# ProPrj_TPS53318-__2025-09-09_17-23-30_20.net
KiCad netlist of a schematic drawn in EasyEDA Pro
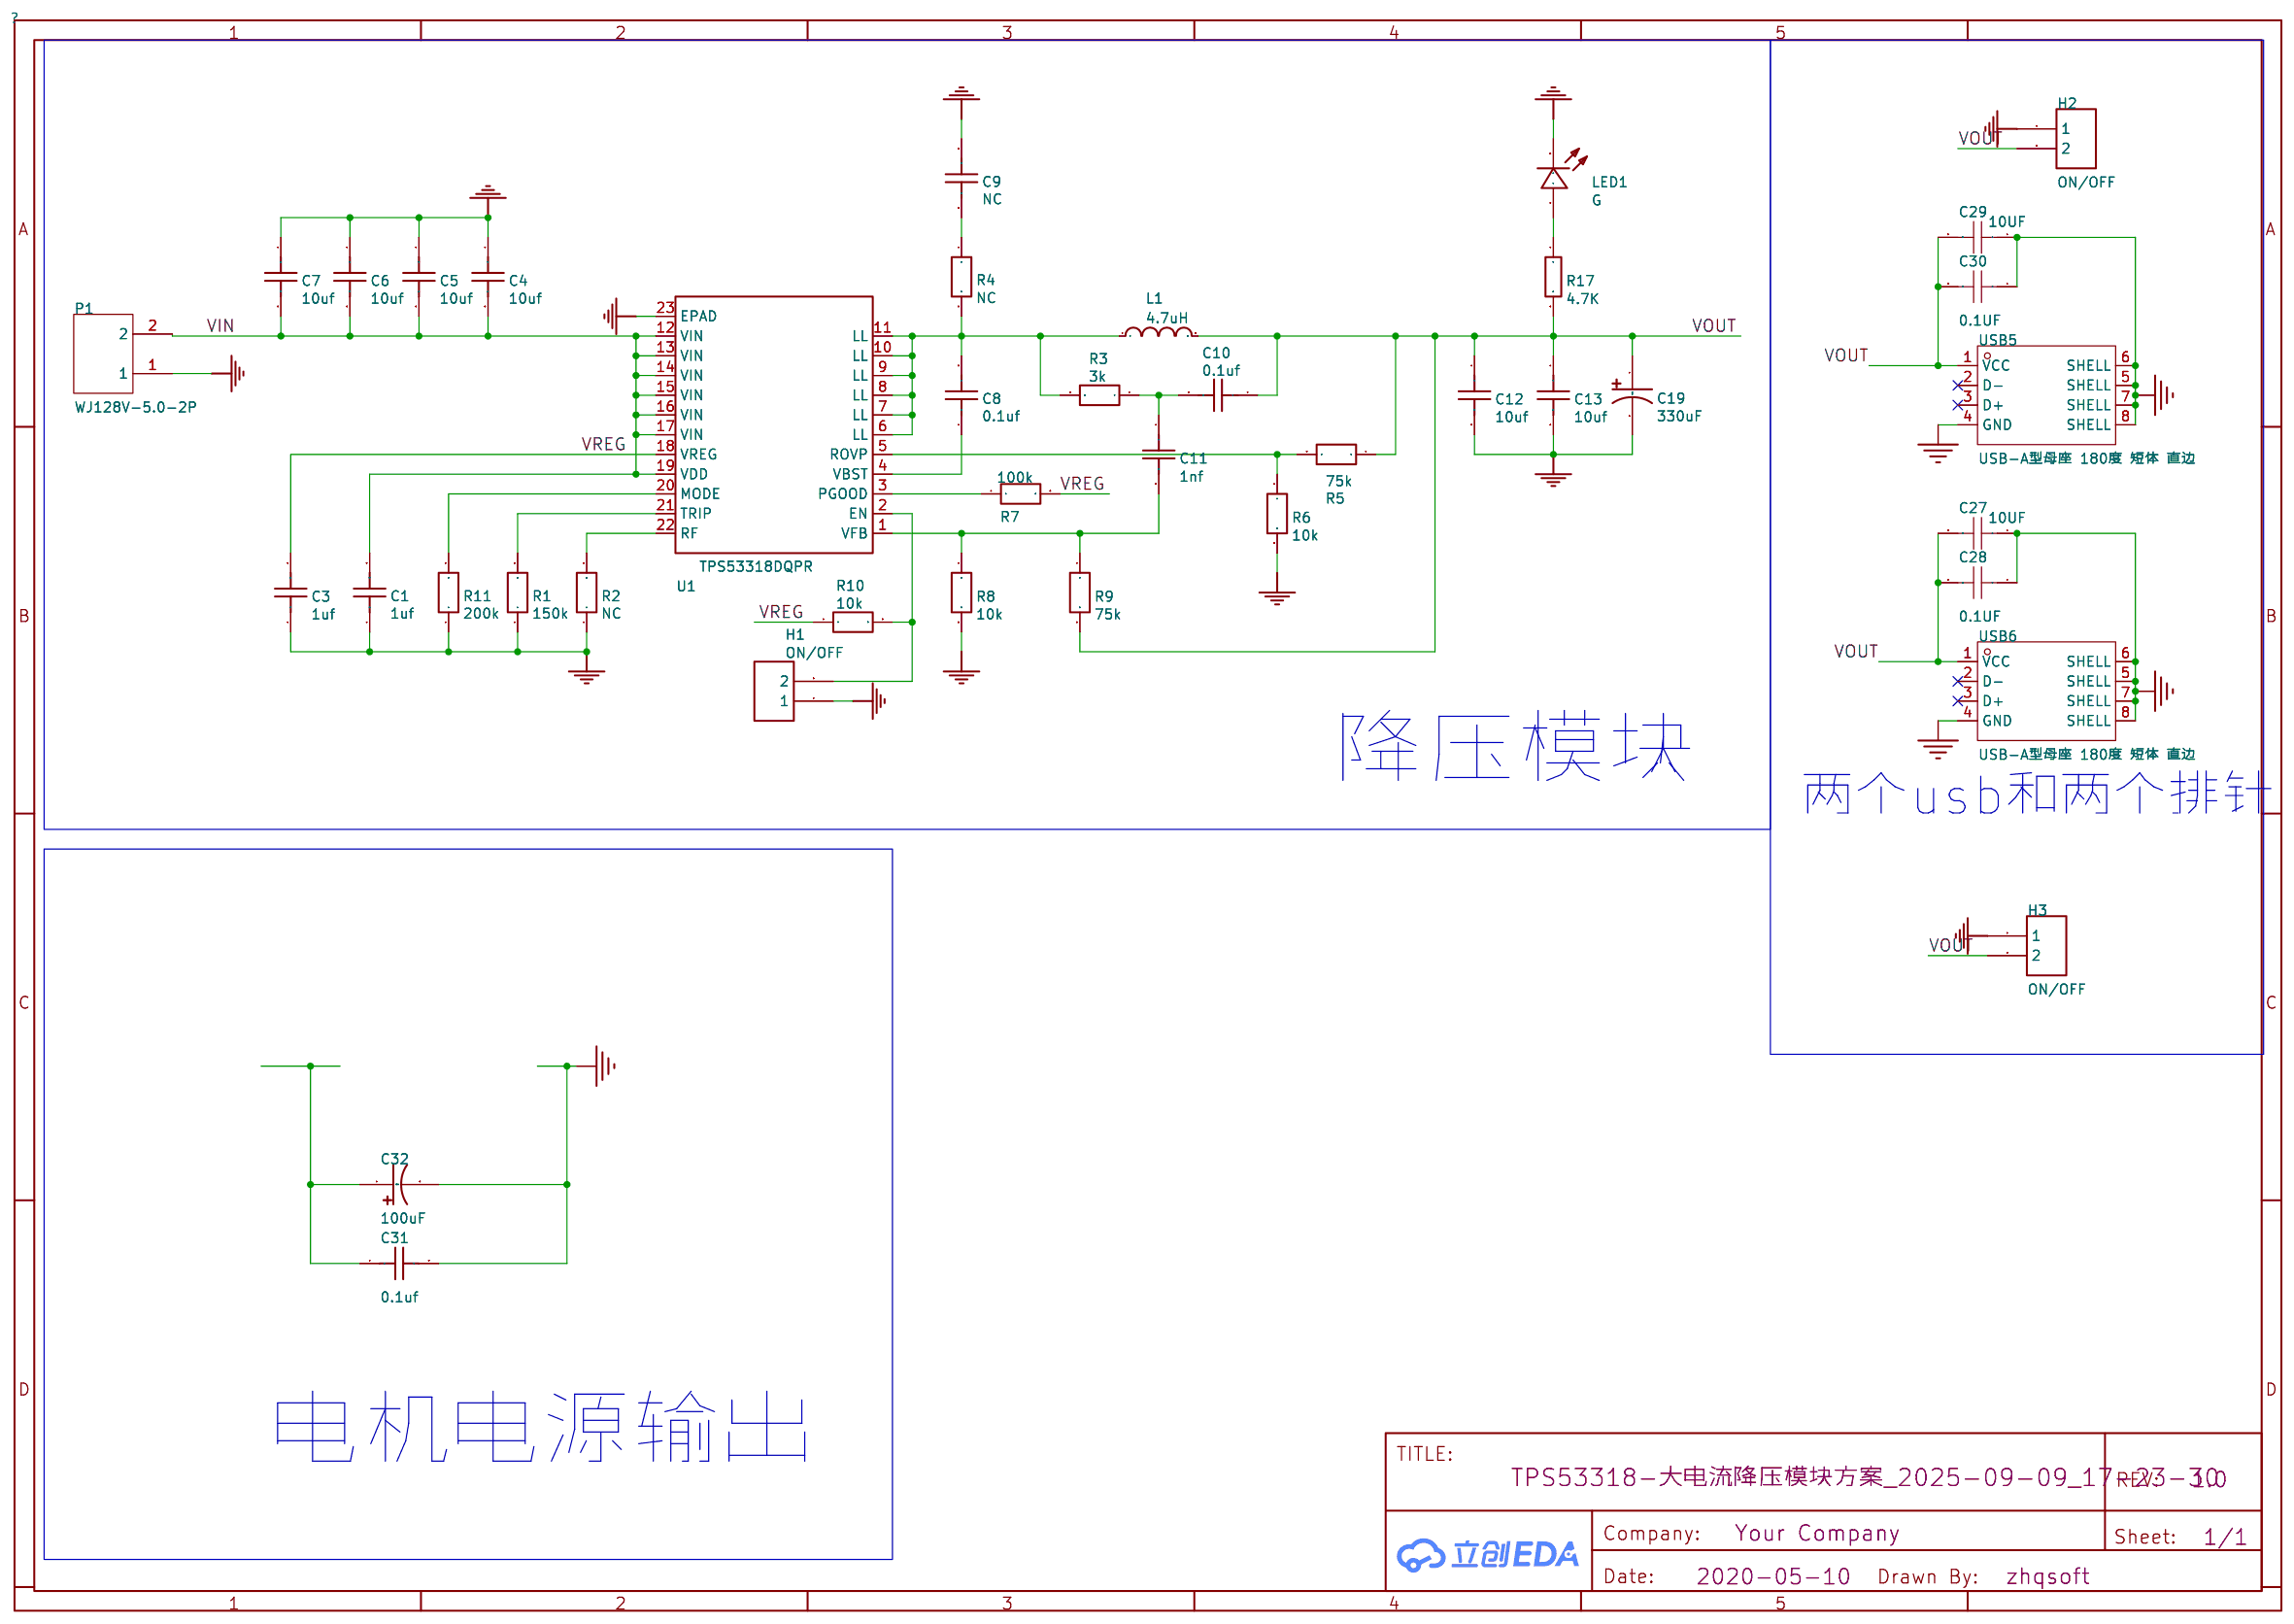
[diagram p0: schematic sheet]

(export (version "E")
  (design (tool "Eeschema 10.0.6"))
  (components
    (comp (ref "C1")
      (value "1uf")
      (fields (field (name "Contributor") "LCEDA_Lib"))
      (libsource (lib "easyedapro") (part "1uf"))
    )
    (comp (ref "C3")
      (value "1uf")
      (fields (field (name "Contributor") "LCEDA_Lib"))
      (libsource (lib "easyedapro") (part "1uf"))
    )
    (comp (ref "C4")
      (value "10uf")
      (fields (field (name "Contributor") "LCEDA_Lib"))
      (libsource (lib "easyedapro") (part "10uf"))
    )
    (comp (ref "C5")
      (value "10uf")
      (fields (field (name "Contributor") "LCEDA_Lib"))
      (libsource (lib "easyedapro") (part "10uf"))
    )
    (comp (ref "C6")
      (value "10uf")
      (fields (field (name "Contributor") "LCEDA_Lib"))
      (libsource (lib "easyedapro") (part "10uf"))
    )
    (comp (ref "C7")
      (value "10uf")
      (fields (field (name "Contributor") "LCEDA_Lib"))
      (libsource (lib "easyedapro") (part "10uf"))
    )
    (comp (ref "C8")
      (value "0.1uf")
      (fields (field (name "Contributor") "LCEDA_Lib"))
      (libsource (lib "easyedapro") (part "0.1uf"))
    )
    (comp (ref "C9")
      (value "NC")
      (fields (field (name "Contributor") "LCEDA_Lib"))
      (libsource (lib "") (part "NC_1"))
    )
    (comp (ref "C10")
      (value "0.1uf")
      (fields (field (name "Contributor") "LCEDA_Lib"))
      (libsource (lib "easyedapro") (part "0.1uf"))
    )
    (comp (ref "C11")
      (value "1nf")
      (fields (field (name "Contributor") "LCEDA_Lib"))
      (libsource (lib "easyedapro") (part "1nf"))
    )
    (comp (ref "C12")
      (value "10uf")
      (fields (field (name "Contributor") "LCEDA_Lib"))
      (libsource (lib "easyedapro") (part "10uf"))
    )
    (comp (ref "C13")
      (value "10uf")
      (fields (field (name "Contributor") "LCEDA_Lib"))
      (libsource (lib "easyedapro") (part "10uf"))
    )
    (comp (ref "C19")
      (value "330uF")
      (fields
        (field (name "Manufacturer Part") "OVZ331M0JTR-0606")
        (field (name "Manufacturer") "LELON")
        (field (name "Contributor") "LCSC")
      )
      (libsource (lib "easyedapro") (part "330uF"))
    )
    (comp (ref "C27")
      (value "10UF")
      (footprint "easyedapro:C0805")
      (libsource (lib "easyedapro") (part "CapAcitance"))
    )
    (comp (ref "C28")
      (value "0.1UF")
      (footprint "easyedapro:C0805")
      (libsource (lib "easyedapro") (part "CapAcitance"))
    )
    (comp (ref "C29")
      (value "10UF")
      (footprint "easyedapro:C0805")
      (libsource (lib "easyedapro") (part "CapAcitance"))
    )
    (comp (ref "C30")
      (value "0.1UF")
      (footprint "easyedapro:C0805")
      (libsource (lib "easyedapro") (part "CapAcitance"))
    )
    (comp (ref "C31")
      (value "0.1uf")
      (fields (field (name "Contributor") "LCEDA_Lib"))
      (libsource (lib "easyedapro") (part "10uf"))
    )
    (comp (ref "C32")
      (value "100uF")
      (fields
        (field (name "Manufacturer Part") "OVZ331M0JTR-0606")
        (field (name "Manufacturer") "LELON")
        (field (name "Contributor") "LCSC")
      )
      (libsource (lib "easyedapro") (part "330uF"))
    )
    (comp (ref "H1")
      (value "ON/OFF")
      (fields (field (name "Manufacturer Part") "3-644456-2") (field (name "Manufacturer") "TE Connectivity"))
      (libsource (lib "easyedapro") (part "ON/OFF"))
    )
    (comp (ref "H2")
      (value "ON/OFF")
      (fields (field (name "Manufacturer Part") "3-644456-2") (field (name "Manufacturer") "TE Connectivity"))
      (libsource (lib "easyedapro") (part "ON/OFF"))
    )
    (comp (ref "H3")
      (value "ON/OFF")
      (fields (field (name "Manufacturer Part") "3-644456-2") (field (name "Manufacturer") "TE Connectivity"))
      (libsource (lib "easyedapro") (part "ON/OFF"))
    )
    (comp (ref "L1")
      (value "4.7uH")
      (fields (field (name "Manufacturer Part") "SMMS1040-4R7M") (field (name "Manufacturer") "SXN"))
      (libsource (lib "easyedapro") (part "4.7uH"))
    )
    (comp (ref "LED1")
      (value "G")
      (fields
        (field (name "Manufacturer Part") "ORH-G36G")
        (field (name "Manufacturer") "Orient")
        (field (name "Contributor") "LCSC")
      )
      (libsource (lib "easyedapro") (part "G"))
    )
    (comp (ref "P1")
      (value "WJ128V-5.0-2P")
      (footprint "easyedapro:CONN-TH_2P-P5.00_WJ128V-5.0-2P")
      (fields (field (name "Manufacturer") "KANGNEX(康奈克斯电气)"))
      (libsource (lib "easyedapro") (part "WJ128V-5.0-2P"))
    )
    (comp (ref "R1")
      (value "150k")
      (fields (field (name "Contributor") "LCEDA_Lib"))
      (libsource (lib "easyedapro") (part "150k"))
    )
    (comp (ref "R2")
      (value "NC")
      (fields (field (name "Contributor") "LCEDA_Lib"))
      (libsource (lib "") (part "NC_2"))
    )
    (comp (ref "R3")
      (value "3k")
      (fields (field (name "Contributor") "LCEDA_Lib"))
      (libsource (lib "easyedapro") (part "3k"))
    )
    (comp (ref "R4")
      (value "NC")
      (fields (field (name "Contributor") "LCEDA_Lib"))
      (libsource (lib "easyedapro") (part "NC"))
    )
    (comp (ref "R5")
      (value "75k")
      (fields (field (name "Contributor") "LCEDA_Lib"))
      (libsource (lib "") (part "75k_1"))
    )
    (comp (ref "R6")
      (value "10k")
      (fields (field (name "Contributor") "LCEDA_Lib"))
      (libsource (lib "easyedapro") (part "10k"))
    )
    (comp (ref "R7")
      (value "100k")
      (fields (field (name "Contributor") "LCEDA_Lib"))
      (libsource (lib "easyedapro") (part "100k"))
    )
    (comp (ref "R8")
      (value "10k")
      (fields (field (name "Contributor") "LCEDA_Lib"))
      (libsource (lib "easyedapro") (part "10k"))
    )
    (comp (ref "R9")
      (value "75k")
      (fields (field (name "Contributor") "LCEDA_Lib"))
      (libsource (lib "easyedapro") (part "75k"))
    )
    (comp (ref "R10")
      (value "10k")
      (fields (field (name "Contributor") "LCEDA_Lib"))
      (libsource (lib "") (part "10k_1"))
    )
    (comp (ref "R11")
      (value "200k")
      (fields (field (name "Contributor") "LCEDA_Lib"))
      (libsource (lib "easyedapro") (part "200k"))
    )
    (comp (ref "R17")
      (value "4.7K")
      (fields
        (field (name "Manufacturer Part") "WR04X4701FTL")
        (field (name "Manufacturer") "WALSIN")
        (field (name "Contributor") "LCSC")
      )
      (libsource (lib "easyedapro") (part "4.7K"))
    )
    (comp (ref "U1")
      (value "TPS53318DQPR")
      (fields (field (name "Manufacturer") "Texas Instruments") (field (name "Contributor") "LCSC"))
      (libsource (lib "easyedapro") (part "TPS53318DQPR"))
    )
    (comp (ref "USB5")
      (value "USB-A型母座 180度 短体 直边")
      (footprint "easyedapro:USB-A-SMD_WT_C9900004571")
      (libsource (lib "easyedapro") (part "USB-A型母座 180度 短体 直边"))
    )
    (comp (ref "USB6")
      (value "USB-A型母座 180度 短体 直边")
      (footprint "easyedapro:USB-A-SMD_WT_C9900004571")
      (libsource (lib "easyedapro") (part "USB-A型母座 180度 短体 直边"))
    )
  )
  (nets
    (net (code "1") (name "/VIN") (class "Default")
      (node (ref "C1") (pin "2") (pinfunction "2_2") (pintype "unspecified"))
      (node (ref "C4") (pin "2") (pinfunction "2_2") (pintype "unspecified"))
      (node (ref "C5") (pin "2") (pinfunction "2_2") (pintype "unspecified"))
      (node (ref "C6") (pin "2") (pinfunction "2_2") (pintype "unspecified"))
      (node (ref "C7") (pin "2") (pinfunction "2_2") (pintype "unspecified"))
      (node (ref "P1") (pin "2") (pinfunction "2_2") (pintype "unspecified"))
      (node (ref "U1") (pin "12") (pinfunction "VIN_12") (pintype "unspecified"))
      (node (ref "U1") (pin "13") (pinfunction "VIN_13") (pintype "unspecified"))
      (node (ref "U1") (pin "14") (pinfunction "VIN_14") (pintype "unspecified"))
      (node (ref "U1") (pin "15") (pinfunction "VIN_15") (pintype "unspecified"))
      (node (ref "U1") (pin "16") (pinfunction "VIN_16") (pintype "unspecified"))
      (node (ref "U1") (pin "17") (pinfunction "VIN_17") (pintype "unspecified"))
      (node (ref "U1") (pin "19") (pinfunction "VDD_19") (pintype "unspecified"))
    )
    (net (code "2") (name "/VOUT") (class "Default")
      (node (ref "C10") (pin "1") (pinfunction "1_1") (pintype "unspecified"))
      (node (ref "C12") (pin "1") (pinfunction "1_1") (pintype "unspecified"))
      (node (ref "C13") (pin "1") (pinfunction "1_1") (pintype "unspecified"))
      (node (ref "C19") (pin "1") (pinfunction "1_1") (pintype "unspecified"))
      (node (ref "C27") (pin "2") (pinfunction "2_2") (pintype "input"))
      (node (ref "C28") (pin "2") (pinfunction "2_2") (pintype "input"))
      (node (ref "C29") (pin "2") (pinfunction "2_2") (pintype "input"))
      (node (ref "C30") (pin "2") (pinfunction "2_2") (pintype "input"))
      (node (ref "H2") (pin "2") (pinfunction "2_2") (pintype "input"))
      (node (ref "H3") (pin "2") (pinfunction "2_2") (pintype "input"))
      (node (ref "L1") (pin "2") (pinfunction "2_2") (pintype "unspecified"))
      (node (ref "R17") (pin "2") (pinfunction "2_2") (pintype "unspecified"))
      (node (ref "R5") (pin "1") (pinfunction "1_1") (pintype "unspecified"))
      (node (ref "R9") (pin "2") (pinfunction "2_2") (pintype "unspecified"))
      (node (ref "USB5") (pin "1") (pinfunction "VCC_1") (pintype "unspecified"))
      (node (ref "USB6") (pin "1") (pinfunction "VCC_1") (pintype "unspecified"))
    )
    (net (code "3") (name "/VREG") (class "Default")
      (node (ref "C3") (pin "2") (pinfunction "2_2") (pintype "unspecified"))
      (node (ref "R10") (pin "1") (pinfunction "1_1") (pintype "unspecified"))
      (node (ref "R7") (pin "2") (pinfunction "2_2") (pintype "unspecified"))
      (node (ref "U1") (pin "18") (pinfunction "VREG_18") (pintype "unspecified"))
    )
    (net (code "4") (name "GND") (class "Default")
      (node (ref "C1") (pin "1") (pinfunction "1_1") (pintype "unspecified"))
      (node (ref "C12") (pin "2") (pinfunction "2_2") (pintype "unspecified"))
      (node (ref "C13") (pin "2") (pinfunction "2_2") (pintype "unspecified"))
      (node (ref "C19") (pin "2") (pinfunction "2_2") (pintype "unspecified"))
      (node (ref "C27") (pin "1") (pinfunction "1_1") (pintype "input"))
      (node (ref "C28") (pin "1") (pinfunction "1_1") (pintype "input"))
      (node (ref "C29") (pin "1") (pinfunction "1_1") (pintype "input"))
      (node (ref "C3") (pin "1") (pinfunction "1_1") (pintype "unspecified"))
      (node (ref "C30") (pin "1") (pinfunction "1_1") (pintype "input"))
      (node (ref "C31") (pin "2") (pinfunction "2_2") (pintype "unspecified"))
      (node (ref "C32") (pin "2") (pinfunction "2_2") (pintype "unspecified"))
      (node (ref "C4") (pin "1") (pinfunction "1_1") (pintype "unspecified"))
      (node (ref "C5") (pin "1") (pinfunction "1_1") (pintype "unspecified"))
      (node (ref "C6") (pin "1") (pinfunction "1_1") (pintype "unspecified"))
      (node (ref "C7") (pin "1") (pinfunction "1_1") (pintype "unspecified"))
      (node (ref "C9") (pin "2") (pinfunction "2_2") (pintype "unspecified"))
      (node (ref "H1") (pin "1") (pinfunction "1_1") (pintype "input"))
      (node (ref "H2") (pin "1") (pinfunction "1_1") (pintype "input"))
      (node (ref "H3") (pin "1") (pinfunction "1_1") (pintype "input"))
      (node (ref "LED1") (pin "2") (pinfunction "K_2") (pintype "unspecified"))
      (node (ref "P1") (pin "1") (pinfunction "1_1") (pintype "unspecified"))
      (node (ref "R1") (pin "1") (pinfunction "1_1") (pintype "unspecified"))
      (node (ref "R11") (pin "1") (pinfunction "1_1") (pintype "unspecified"))
      (node (ref "R2") (pin "1") (pinfunction "1_1") (pintype "unspecified"))
      (node (ref "R6") (pin "2") (pinfunction "2_2") (pintype "unspecified"))
      (node (ref "R8") (pin "2") (pinfunction "2_2") (pintype "unspecified"))
      (node (ref "U1") (pin "23") (pinfunction "EPAD_23") (pintype "unspecified"))
      (node (ref "USB5") (pin "4") (pinfunction "GND_4") (pintype "unspecified"))
      (node (ref "USB5") (pin "5") (pinfunction "SHELL_5") (pintype "unspecified"))
      (node (ref "USB5") (pin "6") (pinfunction "SHELL_6") (pintype "unspecified"))
      (node (ref "USB5") (pin "7") (pinfunction "SHELL_7") (pintype "unspecified"))
      (node (ref "USB5") (pin "8") (pinfunction "SHELL_8") (pintype "unspecified"))
      (node (ref "USB6") (pin "4") (pinfunction "GND_4") (pintype "unspecified"))
      (node (ref "USB6") (pin "5") (pinfunction "SHELL_5") (pintype "unspecified"))
      (node (ref "USB6") (pin "6") (pinfunction "SHELL_6") (pintype "unspecified"))
      (node (ref "USB6") (pin "7") (pinfunction "SHELL_7") (pintype "unspecified"))
      (node (ref "USB6") (pin "8") (pinfunction "SHELL_8") (pintype "unspecified"))
    )
    (net (code "5") (name "Net-(C8-Pad2)") (class "Default")
      (node (ref "C8") (pin "2") (pinfunction "2_2") (pintype "unspecified"))
      (node (ref "L1") (pin "1") (pinfunction "1_1") (pintype "unspecified"))
      (node (ref "R3") (pin "2") (pinfunction "2_2") (pintype "unspecified"))
      (node (ref "R4") (pin "2") (pinfunction "2_2") (pintype "unspecified"))
      (node (ref "U1") (pin "10") (pinfunction "LL_10") (pintype "unspecified"))
      (node (ref "U1") (pin "11") (pinfunction "LL_11") (pintype "unspecified"))
      (node (ref "U1") (pin "6") (pinfunction "LL_6") (pintype "unspecified"))
      (node (ref "U1") (pin "7") (pinfunction "LL_7") (pintype "unspecified"))
      (node (ref "U1") (pin "8") (pinfunction "LL_8") (pintype "unspecified"))
      (node (ref "U1") (pin "9") (pinfunction "LL_9") (pintype "unspecified"))
    )
    (net (code "6") (name "Net-(C9-Pad1)") (class "Default")
      (node (ref "C9") (pin "1") (pinfunction "1_1") (pintype "unspecified"))
      (node (ref "R4") (pin "1") (pinfunction "1_1") (pintype "unspecified"))
    )
    (net (code "7") (name "Net-(C10-Pad2)") (class "Default")
      (node (ref "C10") (pin "2") (pinfunction "2_2") (pintype "unspecified"))
      (node (ref "C11") (pin "1") (pinfunction "1_1") (pintype "unspecified"))
      (node (ref "R3") (pin "1") (pinfunction "1_1") (pintype "unspecified"))
    )
    (net (code "8") (name "Net-(C31-Pad1)") (class "Default")
      (node (ref "C31") (pin "1") (pinfunction "1_1") (pintype "unspecified"))
      (node (ref "C32") (pin "1") (pinfunction "1_1") (pintype "unspecified"))
    )
    (net (code "9") (name "Net-(LED1-A)") (class "Default")
      (node (ref "LED1") (pin "1") (pinfunction "A_1") (pintype "unspecified"))
      (node (ref "R17") (pin "1") (pinfunction "1_1") (pintype "unspecified"))
    )
    (net (code "10") (name "Net-(U1-EN)") (class "Default")
      (node (ref "H1") (pin "2") (pinfunction "2_2") (pintype "input"))
      (node (ref "R10") (pin "2") (pinfunction "2_2") (pintype "unspecified"))
      (node (ref "U1") (pin "2") (pinfunction "EN_2") (pintype "unspecified"))
    )
    (net (code "11") (name "Net-(U1-MODE)") (class "Default")
      (node (ref "R11") (pin "2") (pinfunction "2_2") (pintype "unspecified"))
      (node (ref "U1") (pin "20") (pinfunction "MODE_20") (pintype "unspecified"))
    )
    (net (code "12") (name "Net-(U1-PGOOD)") (class "Default")
      (node (ref "R7") (pin "1") (pinfunction "1_1") (pintype "unspecified"))
      (node (ref "U1") (pin "3") (pinfunction "PGOOD_3") (pintype "unspecified"))
    )
    (net (code "13") (name "Net-(U1-RF)") (class "Default")
      (node (ref "R2") (pin "2") (pinfunction "2_2") (pintype "unspecified"))
      (node (ref "U1") (pin "22") (pinfunction "RF_22") (pintype "unspecified"))
    )
    (net (code "14") (name "Net-(U1-ROVP)") (class "Default")
      (node (ref "R5") (pin "2") (pinfunction "2_2") (pintype "unspecified"))
      (node (ref "R6") (pin "1") (pinfunction "1_1") (pintype "unspecified"))
      (node (ref "U1") (pin "5") (pinfunction "ROVP_5") (pintype "unspecified"))
    )
    (net (code "15") (name "Net-(U1-TRIP)") (class "Default")
      (node (ref "R1") (pin "2") (pinfunction "2_2") (pintype "unspecified"))
      (node (ref "U1") (pin "21") (pinfunction "TRIP_21") (pintype "unspecified"))
    )
    (net (code "16") (name "Net-(U1-VBST)") (class "Default")
      (node (ref "C8") (pin "1") (pinfunction "1_1") (pintype "unspecified"))
      (node (ref "U1") (pin "4") (pinfunction "VBST_4") (pintype "unspecified"))
    )
    (net (code "17") (name "Net-(U1-VFB)") (class "Default")
      (node (ref "C11") (pin "2") (pinfunction "2_2") (pintype "unspecified"))
      (node (ref "R8") (pin "1") (pinfunction "1_1") (pintype "unspecified"))
      (node (ref "R9") (pin "1") (pinfunction "1_1") (pintype "unspecified"))
      (node (ref "U1") (pin "1") (pinfunction "VFB_1") (pintype "unspecified"))
    )
    (net (code "18") (name "unconnected-(USB5-D+-Pad3)") (class "Default")
      (node (ref "USB5") (pin "3") (pinfunction "D+_3") (pintype "unspecified+no_connect"))
    )
    (net (code "19") (name "unconnected-(USB5-D--Pad2)") (class "Default")
      (node (ref "USB5") (pin "2") (pinfunction "D-_2") (pintype "unspecified+no_connect"))
    )
    (net (code "20") (name "unconnected-(USB6-D+-Pad3)") (class "Default")
      (node (ref "USB6") (pin "3") (pinfunction "D+_3") (pintype "unspecified+no_connect"))
    )
    (net (code "21") (name "unconnected-(USB6-D--Pad2)") (class "Default")
      (node (ref "USB6") (pin "2") (pinfunction "D-_2") (pintype "unspecified+no_connect"))
    )
  )
)
